# VNT.net
KiCad netlist of a schematic drawn in EAGLE
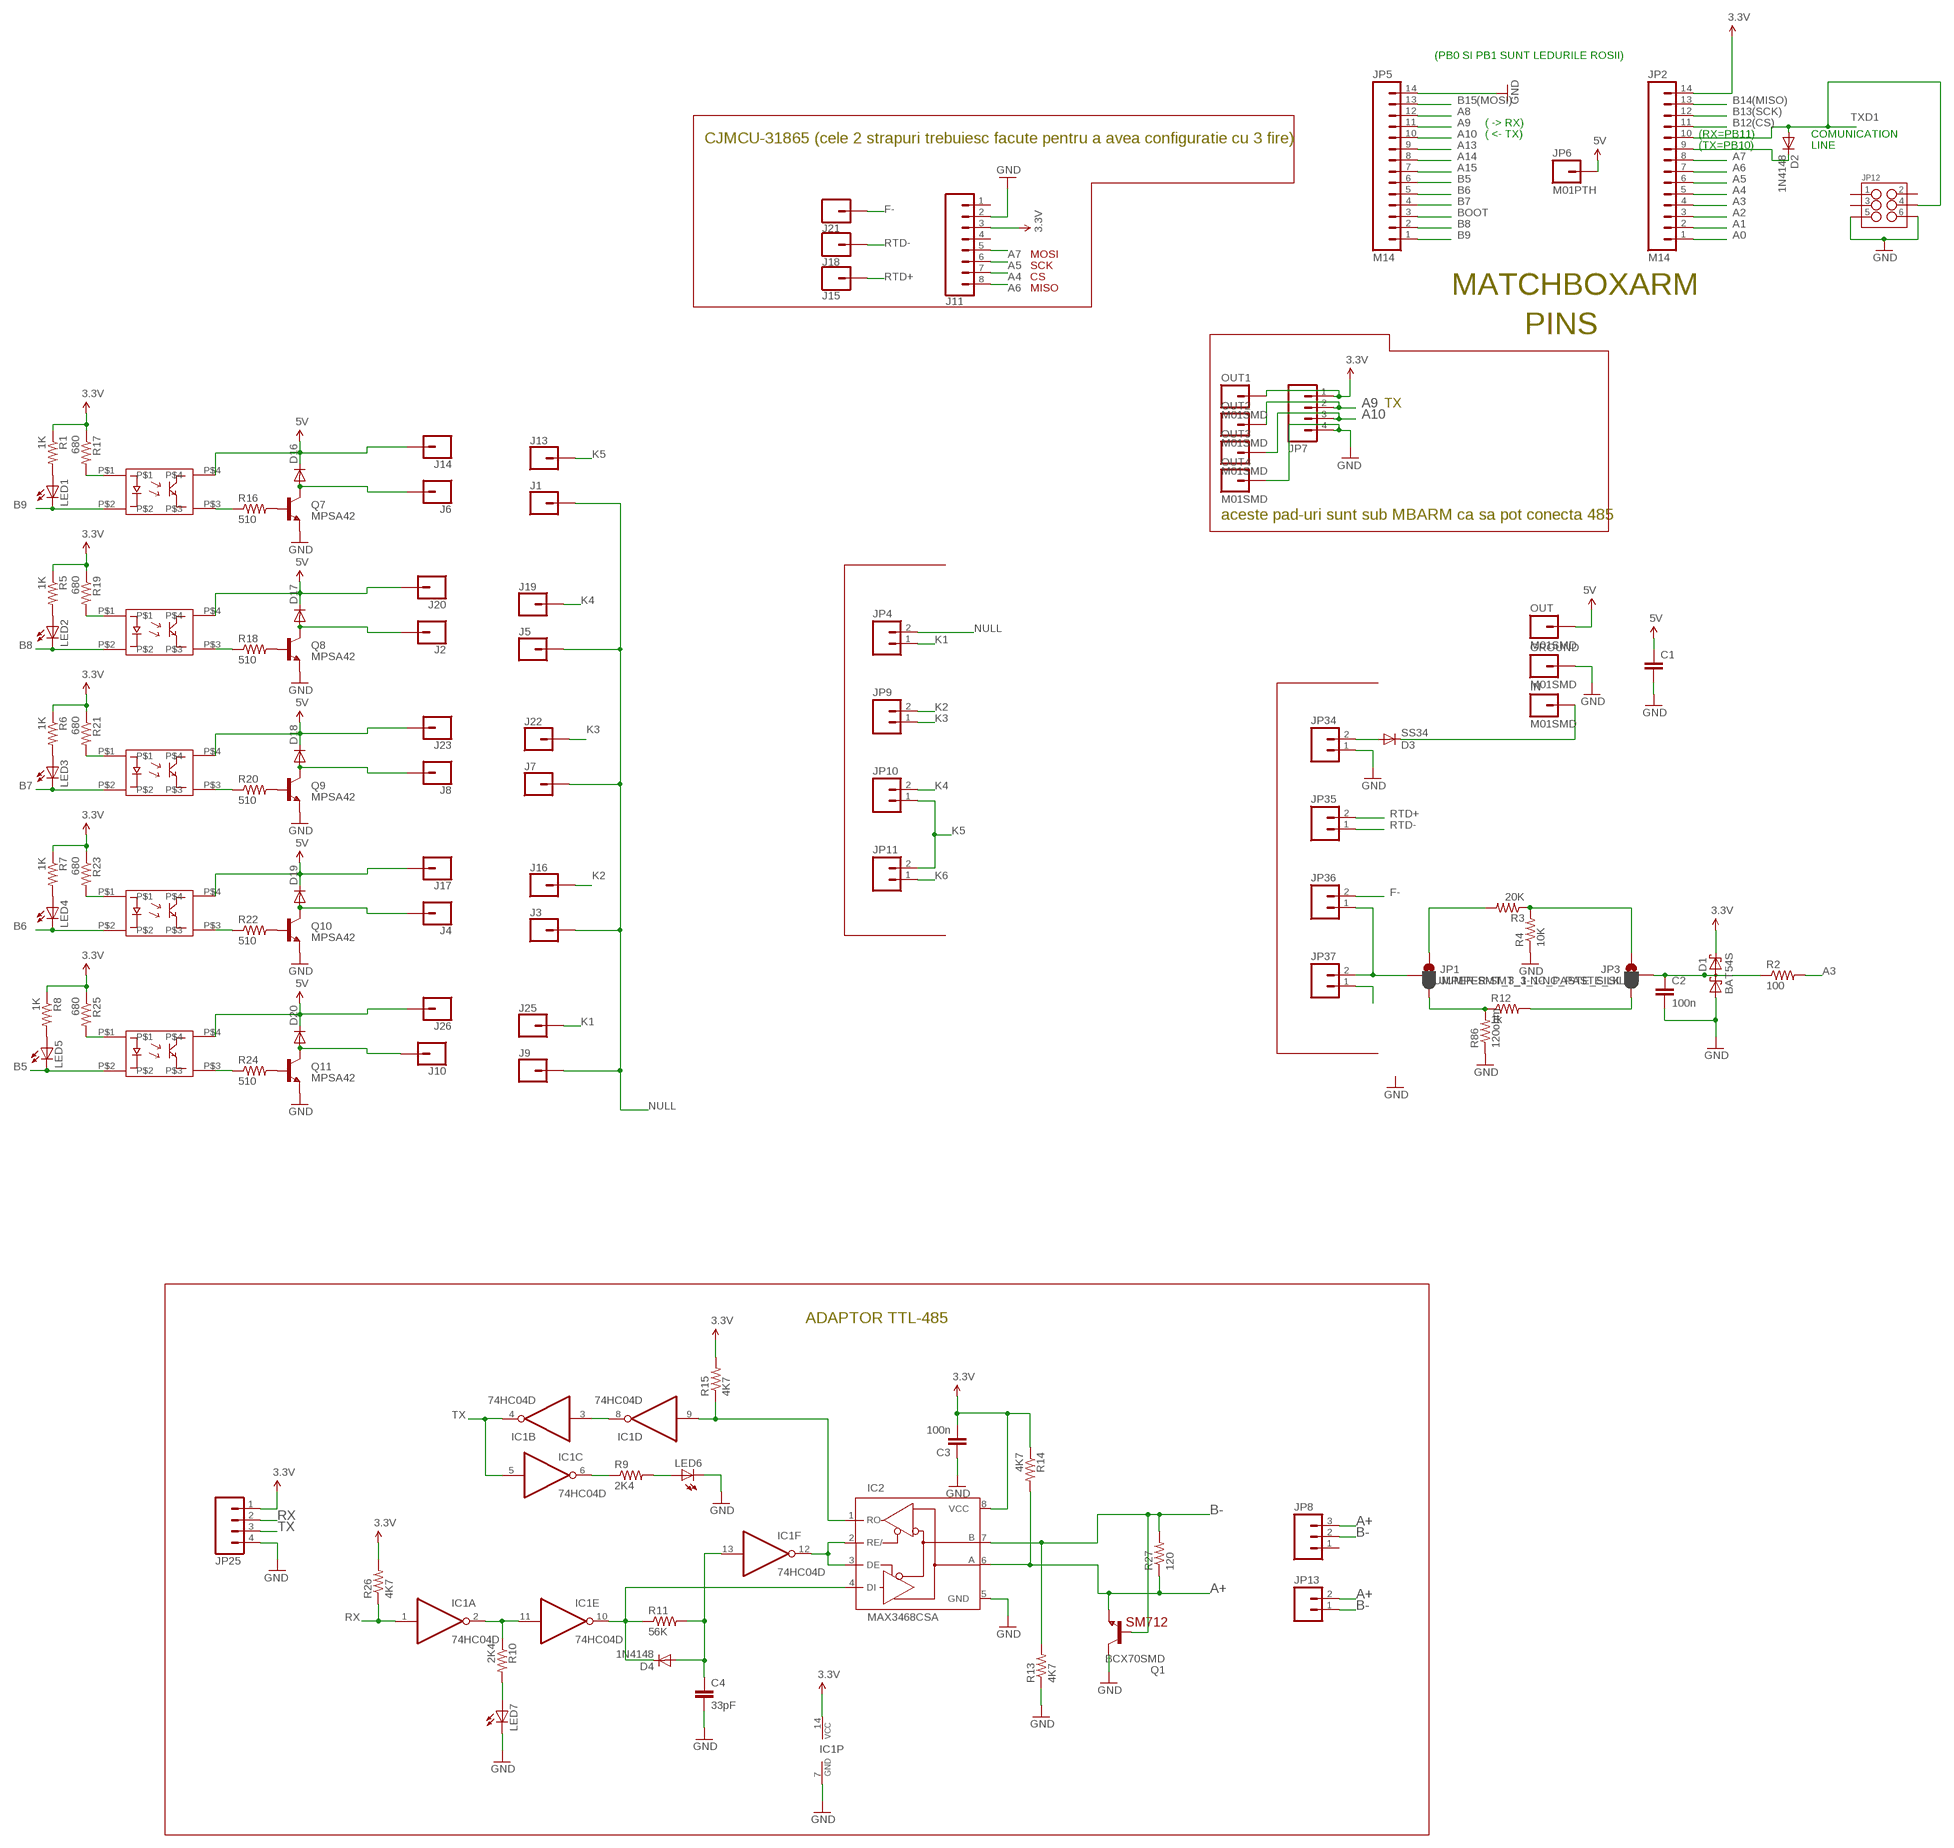
[diagram p0: schematic, sheet 1]

(export (version "E")
  (design (tool "Eeschema 10.0.6"))
  (components
    (comp (ref "C1")
      (value "CAPPTH1")
      (footprint "eagle-import:CAP-PTH-5MM")
      (libsource (lib "eagle-import") (part "CAPPTH1"))
    )
    (comp (ref "C2")
      (value "100n")
      (footprint "eagle-import:0805")
      (libsource (lib "eagle-import") (part "CAP0805"))
    )
    (comp (ref "C3")
      (value "100n")
      (footprint "eagle-import:0805")
      (libsource (lib "eagle-import") (part "CAP0805"))
    )
    (comp (ref "C4")
      (value "33pF")
      (footprint "eagle-import:0805")
      (libsource (lib "eagle-import") (part "CAP0805"))
    )
    (comp (ref "D1")
      (value "BAT54S")
      (footprint "eagle-import:SOT23")
      (libsource (lib "eagle-import") (part "BAT54S"))
    )
    (comp (ref "D2")
      (value "1N4148")
      (footprint "eagle-import:MINIMELF")
      (libsource (lib "eagle-import") (part "DIODE-MINIMELF"))
    )
    (comp (ref "D3")
      (value "SS34")
      (footprint "eagle-import:SMC")
      (libsource (lib "eagle-import") (part "DIODE-SMC"))
    )
    (comp (ref "D4")
      (value "1N4148")
      (footprint "eagle-import:MINIMELF")
      (libsource (lib "eagle-import") (part "DIODE-MINIMELF"))
    )
    (comp (ref "D16")
      (value "DIODE-MINIMELF")
      (footprint "eagle-import:MINIMELF")
      (libsource (lib "eagle-import") (part "diode_NEDELCU_DIODE-MINIMELF"))
    )
    (comp (ref "D17")
      (value "DIODE-MINIMELF")
      (footprint "eagle-import:MINIMELF")
      (libsource (lib "eagle-import") (part "diode_NEDELCU_DIODE-MINIMELF"))
    )
    (comp (ref "D18")
      (value "DIODE-MINIMELF")
      (footprint "eagle-import:MINIMELF")
      (libsource (lib "eagle-import") (part "diode_NEDELCU_DIODE-MINIMELF"))
    )
    (comp (ref "D19")
      (value "DIODE-MINIMELF")
      (footprint "eagle-import:MINIMELF")
      (libsource (lib "eagle-import") (part "diode_NEDELCU_DIODE-MINIMELF"))
    )
    (comp (ref "D20")
      (value "DIODE-MINIMELF")
      (footprint "eagle-import:MINIMELF")
      (libsource (lib "eagle-import") (part "diode_NEDELCU_DIODE-MINIMELF"))
    )
    (comp (ref "GROUND")
      (value "M01SMD")
      (footprint "eagle-import:LUXEON-PAD")
      (libsource (lib "eagle-import") (part "M01SMD"))
    )
    (comp (ref "IC1")
      (value "74HC04D")
      (footprint "eagle-import:SO14")
      (libsource (lib "eagle-import") (part "7404DHC"))
    )
    (comp (ref "IC2")
      (value "MAX3468CSA")
      (footprint "eagle-import:SO08")
      (fields (field (name "MPN") "MAX3468CSA+"))
      (libsource (lib "eagle-import") (part "MAX34SA68C"))
    )
    (comp (ref "IN")
      (value "M01SMD")
      (footprint "eagle-import:LUXEON-PAD")
      (libsource (lib "eagle-import") (part "M01SMD"))
    )
    (comp (ref "J1")
      (value "CONN_01")
      (footprint "eagle-import:1X01@2")
      (libsource (lib "eagle-import") (part "CONN_01"))
    )
    (comp (ref "J2")
      (value "CONN_01")
      (footprint "eagle-import:1X01@2")
      (libsource (lib "eagle-import") (part "CONN_01"))
    )
    (comp (ref "J3")
      (value "CONN_01")
      (footprint "eagle-import:1X01@2")
      (libsource (lib "eagle-import") (part "CONN_01"))
    )
    (comp (ref "J4")
      (value "CONN_01")
      (footprint "eagle-import:1X01@2")
      (libsource (lib "eagle-import") (part "CONN_01"))
    )
    (comp (ref "J5")
      (value "CONN_01")
      (footprint "eagle-import:1X01@2")
      (libsource (lib "eagle-import") (part "CONN_01"))
    )
    (comp (ref "J6")
      (value "CONN_01")
      (footprint "eagle-import:1X01@2")
      (libsource (lib "eagle-import") (part "CONN_01"))
    )
    (comp (ref "J7")
      (value "CONN_01")
      (footprint "eagle-import:1X01@2")
      (libsource (lib "eagle-import") (part "CONN_01"))
    )
    (comp (ref "J8")
      (value "CONN_01")
      (footprint "eagle-import:1X01@2")
      (libsource (lib "eagle-import") (part "CONN_01"))
    )
    (comp (ref "J9")
      (value "CONN_01")
      (footprint "eagle-import:1X01@2")
      (libsource (lib "eagle-import") (part "CONN_01"))
    )
    (comp (ref "J10")
      (value "CONN_01")
      (footprint "eagle-import:1X01@2")
      (libsource (lib "eagle-import") (part "CONN_01"))
    )
    (comp (ref "J11")
      (value "CONN_08LOCK")
      (footprint "eagle-import:1X08_LOCK")
      (libsource (lib "eagle-import") (part "CONN_08LOCK"))
    )
    (comp (ref "J13")
      (value "CONN_01")
      (footprint "eagle-import:1X01@2")
      (libsource (lib "eagle-import") (part "CONN_01"))
    )
    (comp (ref "J14")
      (value "CONN_01")
      (footprint "eagle-import:1X01@2")
      (libsource (lib "eagle-import") (part "CONN_01"))
    )
    (comp (ref "J15")
      (value "CONN_01")
      (footprint "eagle-import:1X01@2")
      (libsource (lib "eagle-import") (part "CONN_01"))
    )
    (comp (ref "J16")
      (value "CONN_01")
      (footprint "eagle-import:1X01@2")
      (libsource (lib "eagle-import") (part "CONN_01"))
    )
    (comp (ref "J17")
      (value "CONN_01")
      (footprint "eagle-import:1X01@2")
      (libsource (lib "eagle-import") (part "CONN_01"))
    )
    (comp (ref "J18")
      (value "CONN_01")
      (footprint "eagle-import:1X01@2")
      (libsource (lib "eagle-import") (part "CONN_01"))
    )
    (comp (ref "J19")
      (value "CONN_01")
      (footprint "eagle-import:1X01@2")
      (libsource (lib "eagle-import") (part "CONN_01"))
    )
    (comp (ref "J20")
      (value "CONN_01")
      (footprint "eagle-import:1X01@2")
      (libsource (lib "eagle-import") (part "CONN_01"))
    )
    (comp (ref "J21")
      (value "CONN_01")
      (footprint "eagle-import:1X01@2")
      (libsource (lib "eagle-import") (part "CONN_01"))
    )
    (comp (ref "J22")
      (value "CONN_01")
      (footprint "eagle-import:1X01@2")
      (libsource (lib "eagle-import") (part "CONN_01"))
    )
    (comp (ref "J23")
      (value "CONN_01")
      (footprint "eagle-import:1X01@2")
      (libsource (lib "eagle-import") (part "CONN_01"))
    )
    (comp (ref "J25")
      (value "CONN_01")
      (footprint "eagle-import:1X01@2")
      (libsource (lib "eagle-import") (part "CONN_01"))
    )
    (comp (ref "J26")
      (value "CONN_01")
      (footprint "eagle-import:1X01@2")
      (libsource (lib "eagle-import") (part "CONN_01"))
    )
    (comp (ref "JP1")
      (value "JUMPER-SMT_3_1-NC_PASTE_SILK")
      (footprint "eagle-import:SMT-JUMPER_3_1-NC_PASTE_SILK")
      (libsource (lib "eagle-import") (part "JUMPER-SMT_3_1-NC_PASTE_SILK"))
    )
    (comp (ref "JP2")
      (value "M14")
      (footprint "eagle-import:1X14")
      (libsource (lib "eagle-import") (part "M14"))
    )
    (comp (ref "JP3")
      (value "JUMPER-SMT_3_1-NC_PASTE_SILK")
      (footprint "eagle-import:SMT-JUMPER_3_1-NC_PASTE_SILK")
      (libsource (lib "eagle-import") (part "JUMPER-SMT_3_1-NC_PASTE_SILK"))
    )
    (comp (ref "JP4")
      (value "M025MM")
      (footprint "eagle-import:SCREWTERMINAL-5MM-2")
      (libsource (lib "eagle-import") (part "M025MM"))
    )
    (comp (ref "JP5")
      (value "M14")
      (footprint "eagle-import:1X14")
      (libsource (lib "eagle-import") (part "M14"))
    )
    (comp (ref "JP6")
      (value "M01PTH")
      (footprint "eagle-import:1X01")
      (libsource (lib "eagle-import") (part "M01PTH"))
    )
    (comp (ref "JP7")
      (value "M04PTH")
      (footprint "eagle-import:1X04")
      (libsource (lib "eagle-import") (part "M04PTH"))
    )
    (comp (ref "JP8")
      (value "M03-SCREW-5MM")
      (footprint "eagle-import:SCREWTERMINAL-5MM-3")
      (libsource (lib "eagle-import") (part "M03-SCREW-5MM"))
    )
    (comp (ref "JP9")
      (value "M025MM")
      (footprint "eagle-import:SCREWTERMINAL-5MM-2")
      (libsource (lib "eagle-import") (part "M025MM"))
    )
    (comp (ref "JP10")
      (value "M025MM")
      (footprint "eagle-import:SCREWTERMINAL-5MM-2")
      (libsource (lib "eagle-import") (part "M025MM"))
    )
    (comp (ref "JP11")
      (value "M025MM")
      (footprint "eagle-import:SCREWTERMINAL-5MM-2")
      (libsource (lib "eagle-import") (part "M025MM"))
    )
    (comp (ref "JP12")
      (value "M03X22X3_SILK_MALE_PTH")
      (footprint "eagle-import:2X3")
      (libsource (lib "eagle-import") (part "M03X22X3_SILK_MALE_PTH"))
    )
    (comp (ref "JP13")
      (value "M025MM")
      (footprint "eagle-import:SCREWTERMINAL-5MM-2")
      (libsource (lib "eagle-import") (part "M025MM"))
    )
    (comp (ref "JP25")
      (value "M04PTH")
      (footprint "eagle-import:1X04")
      (libsource (lib "eagle-import") (part "M04PTH"))
    )
    (comp (ref "JP34")
      (value "M025MM")
      (footprint "eagle-import:SCREWTERMINAL-5MM-2")
      (libsource (lib "eagle-import") (part "M025MM"))
    )
    (comp (ref "JP35")
      (value "M025MM")
      (footprint "eagle-import:SCREWTERMINAL-5MM-2")
      (libsource (lib "eagle-import") (part "M025MM"))
    )
    (comp (ref "JP36")
      (value "M025MM")
      (footprint "eagle-import:SCREWTERMINAL-5MM-2")
      (libsource (lib "eagle-import") (part "M025MM"))
    )
    (comp (ref "JP37")
      (value "M025MM")
      (footprint "eagle-import:SCREWTERMINAL-5MM-2")
      (libsource (lib "eagle-import") (part "M025MM"))
    )
    (comp (ref "LED1")
      (value "LEDCHIP-LED0805")
      (footprint "eagle-import:CHIP-LED0805")
      (libsource (lib "eagle-import") (part "LEDCHIP-LED0805"))
    )
    (comp (ref "LED2")
      (value "LEDCHIP-LED0805")
      (footprint "eagle-import:CHIP-LED0805")
      (libsource (lib "eagle-import") (part "LEDCHIP-LED0805"))
    )
    (comp (ref "LED3")
      (value "LEDCHIP-LED0805")
      (footprint "eagle-import:CHIP-LED0805")
      (libsource (lib "eagle-import") (part "LEDCHIP-LED0805"))
    )
    (comp (ref "LED4")
      (value "LEDCHIP-LED0805")
      (footprint "eagle-import:CHIP-LED0805")
      (libsource (lib "eagle-import") (part "LEDCHIP-LED0805"))
    )
    (comp (ref "LED5")
      (value "LEDCHIP-LED0805")
      (footprint "eagle-import:CHIP-LED0805")
      (libsource (lib "eagle-import") (part "LEDCHIP-LED0805"))
    )
    (comp (ref "LED6")
      (value "LEDCHIP-LED0805")
      (footprint "eagle-import:CHIP-LED0805")
      (libsource (lib "eagle-import") (part "LEDCHIP-LED0805"))
    )
    (comp (ref "LED7")
      (value "LEDCHIP-LED0805")
      (footprint "eagle-import:CHIP-LED0805")
      (libsource (lib "eagle-import") (part "LEDCHIP-LED0805"))
    )
    (comp (ref "OUT")
      (value "M01SMD")
      (footprint "eagle-import:LUXEON-PAD")
      (libsource (lib "eagle-import") (part "M01SMD"))
    )
    (comp (ref "OUT1")
      (value "M01SMD")
      (footprint "eagle-import:LUXEON-PAD")
      (libsource (lib "eagle-import") (part "M01SMD"))
    )
    (comp (ref "OUT2")
      (value "M01SMD")
      (footprint "eagle-import:LUXEON-PAD")
      (libsource (lib "eagle-import") (part "M01SMD"))
    )
    (comp (ref "OUT3")
      (value "M01SMD")
      (footprint "eagle-import:LUXEON-PAD")
      (libsource (lib "eagle-import") (part "M01SMD"))
    )
    (comp (ref "OUT4")
      (value "M01SMD")
      (footprint "eagle-import:LUXEON-PAD")
      (libsource (lib "eagle-import") (part "M01SMD"))
    )
    (comp (ref "Q1")
      (value "BCX70SMD")
      (footprint "eagle-import:SOT23")
      (libsource (lib "eagle-import") (part "BCX70SMD"))
    )
    (comp (ref "Q7")
      (value "MPSA42")
      (footprint "eagle-import:SOT23-3")
      (libsource (lib "eagle-import") (part "TRANSISTOR_NPNMPSA42"))
    )
    (comp (ref "Q8")
      (value "MPSA42")
      (footprint "eagle-import:SOT23-3")
      (libsource (lib "eagle-import") (part "TRANSISTOR_NPNMPSA42"))
    )
    (comp (ref "Q9")
      (value "MPSA42")
      (footprint "eagle-import:SOT23-3")
      (libsource (lib "eagle-import") (part "TRANSISTOR_NPNMPSA42"))
    )
    (comp (ref "Q10")
      (value "MPSA42")
      (footprint "eagle-import:SOT23-3")
      (libsource (lib "eagle-import") (part "TRANSISTOR_NPNMPSA42"))
    )
    (comp (ref "Q11")
      (value "MPSA42")
      (footprint "eagle-import:SOT23-3")
      (libsource (lib "eagle-import") (part "TRANSISTOR_NPNMPSA42"))
    )
    (comp (ref "R1")
      (value "1K")
      (footprint "eagle-import:0805")
      (libsource (lib "eagle-import") (part "RESISTOR0805-RES"))
    )
    (comp (ref "R2")
      (value "100")
      (footprint "eagle-import:0805")
      (libsource (lib "eagle-import") (part "RESISTOR0805-RES"))
    )
    (comp (ref "R3")
      (value "20K")
      (footprint "eagle-import:1206")
      (libsource (lib "eagle-import") (part "RESISTOR1206"))
    )
    (comp (ref "R4")
      (value "10K")
      (footprint "eagle-import:1206")
      (libsource (lib "eagle-import") (part "RESISTOR1206"))
    )
    (comp (ref "R5")
      (value "1K")
      (footprint "eagle-import:0805")
      (libsource (lib "eagle-import") (part "RESISTOR0805-RES"))
    )
    (comp (ref "R6")
      (value "1K")
      (footprint "eagle-import:0805")
      (libsource (lib "eagle-import") (part "RESISTOR0805-RES"))
    )
    (comp (ref "R7")
      (value "1K")
      (footprint "eagle-import:0805")
      (libsource (lib "eagle-import") (part "RESISTOR0805-RES"))
    )
    (comp (ref "R8")
      (value "1K")
      (footprint "eagle-import:0805")
      (libsource (lib "eagle-import") (part "RESISTOR0805-RES"))
    )
    (comp (ref "R9")
      (value "2K4")
      (footprint "eagle-import:0805")
      (libsource (lib "eagle-import") (part "RESISTOR0805-RES"))
    )
    (comp (ref "R10")
      (value "2K4")
      (footprint "eagle-import:0805")
      (libsource (lib "eagle-import") (part "RESISTOR0805-RES"))
    )
    (comp (ref "R11")
      (value "56K")
      (footprint "eagle-import:0805")
      (libsource (lib "eagle-import") (part "RESISTOR0805-RES"))
    )
    (comp (ref "R12")
      (value "1k")
      (footprint "eagle-import:0805")
      (libsource (lib "eagle-import") (part "RESISTOR0805-RES"))
    )
    (comp (ref "R13")
      (value "4K7")
      (footprint "eagle-import:0805")
      (libsource (lib "eagle-import") (part "RESISTOR0805-RES"))
    )
    (comp (ref "R14")
      (value "4K7")
      (footprint "eagle-import:0805")
      (libsource (lib "eagle-import") (part "RESISTOR0805-RES"))
    )
    (comp (ref "R15")
      (value "4K7")
      (footprint "eagle-import:0805")
      (libsource (lib "eagle-import") (part "RESISTOR0805-RES"))
    )
    (comp (ref "R16")
      (value "510")
      (footprint "eagle-import:0805")
      (libsource (lib "eagle-import") (part "RESISTOR0805-RES"))
    )
    (comp (ref "R17")
      (value "680")
      (footprint "eagle-import:0805")
      (libsource (lib "eagle-import") (part "RESISTOR0805-RES"))
    )
    (comp (ref "R18")
      (value "510")
      (footprint "eagle-import:0805")
      (libsource (lib "eagle-import") (part "RESISTOR0805-RES"))
    )
    (comp (ref "R19")
      (value "680")
      (footprint "eagle-import:0805")
      (libsource (lib "eagle-import") (part "RESISTOR0805-RES"))
    )
    (comp (ref "R20")
      (value "510")
      (footprint "eagle-import:0805")
      (libsource (lib "eagle-import") (part "RESISTOR0805-RES"))
    )
    (comp (ref "R21")
      (value "680")
      (footprint "eagle-import:0805")
      (libsource (lib "eagle-import") (part "RESISTOR0805-RES"))
    )
    (comp (ref "R22")
      (value "510")
      (footprint "eagle-import:0805")
      (libsource (lib "eagle-import") (part "RESISTOR0805-RES"))
    )
    (comp (ref "R23")
      (value "680")
      (footprint "eagle-import:0805")
      (libsource (lib "eagle-import") (part "RESISTOR0805-RES"))
    )
    (comp (ref "R24")
      (value "510")
      (footprint "eagle-import:0805")
      (libsource (lib "eagle-import") (part "RESISTOR0805-RES"))
    )
    (comp (ref "R25")
      (value "680")
      (footprint "eagle-import:0805")
      (libsource (lib "eagle-import") (part "RESISTOR0805-RES"))
    )
    (comp (ref "R26")
      (value "4K7")
      (footprint "eagle-import:0805")
      (libsource (lib "eagle-import") (part "RESISTOR0805-RES"))
    )
    (comp (ref "R27")
      (value "120")
      (footprint "eagle-import:0805")
      (libsource (lib "eagle-import") (part "RESISTOR0805-RES"))
    )
    (comp (ref "R86")
      (value "120ohm")
      (footprint "eagle-import:R2010")
      (libsource (lib "eagle-import") (part "RESISTOR2010"))
    )
    (comp (ref "U$13")
      (value "IS181D-I")
      (footprint "eagle-import:TLP181-I")
      (libsource (lib "eagle-import") (part "IS181D-I"))
    )
    (comp (ref "U$14")
      (value "IS181D-I")
      (footprint "eagle-import:TLP181-I")
      (libsource (lib "eagle-import") (part "IS181D-I"))
    )
    (comp (ref "U$15")
      (value "IS181D-I")
      (footprint "eagle-import:TLP181-I")
      (libsource (lib "eagle-import") (part "IS181D-I"))
    )
    (comp (ref "U$16")
      (value "IS181D-I")
      (footprint "eagle-import:TLP181-I")
      (libsource (lib "eagle-import") (part "IS181D-I"))
    )
    (comp (ref "U$17")
      (value "IS181D-I")
      (footprint "eagle-import:TLP181-I")
      (libsource (lib "eagle-import") (part "IS181D-I"))
    )
  )
  (nets
    (net (code "1") (name "/A+") (class "Default")
      (node (ref "IC2") (pin "6") (pinfunction "A_6") (pintype "passive"))
      (node (ref "JP13") (pin "2") (pinfunction "2_2") (pintype "passive"))
      (node (ref "JP8") (pin "3") (pinfunction "3_3") (pintype "passive"))
      (node (ref "Q1") (pin "2") (pinfunction "E_2") (pintype "passive"))
      (node (ref "R14") (pin "2") (pinfunction "2_2") (pintype "passive"))
      (node (ref "R27") (pin "1") (pinfunction "1_1") (pintype "passive"))
    )
    (net (code "2") (name "/A0") (class "Default")
      (node (ref "JP2") (pin "1") (pinfunction "1_1") (pintype "passive"))
    )
    (net (code "3") (name "/A1") (class "Default")
      (node (ref "JP2") (pin "2") (pinfunction "2_2") (pintype "passive"))
    )
    (net (code "4") (name "/A2") (class "Default")
      (node (ref "JP2") (pin "3") (pinfunction "3_3") (pintype "passive"))
    )
    (net (code "5") (name "/A3") (class "Default")
      (node (ref "JP2") (pin "4") (pinfunction "4_4") (pintype "passive"))
      (node (ref "R2") (pin "2") (pinfunction "2_2") (pintype "passive"))
    )
    (net (code "6") (name "/A4") (class "Default")
      (node (ref "J11") (pin "7") (pinfunction "7_7") (pintype "passive"))
      (node (ref "JP2") (pin "5") (pinfunction "5_5") (pintype "passive"))
    )
    (net (code "7") (name "/A5") (class "Default")
      (node (ref "J11") (pin "6") (pinfunction "6_6") (pintype "passive"))
      (node (ref "JP2") (pin "6") (pinfunction "6_6") (pintype "passive"))
    )
    (net (code "8") (name "/A6") (class "Default")
      (node (ref "J11") (pin "8") (pinfunction "8_8") (pintype "passive"))
      (node (ref "JP2") (pin "7") (pinfunction "7_7") (pintype "passive"))
    )
    (net (code "9") (name "/A7") (class "Default")
      (node (ref "J11") (pin "5") (pinfunction "5_5") (pintype "passive"))
      (node (ref "JP2") (pin "8") (pinfunction "8_8") (pintype "passive"))
    )
    (net (code "10") (name "/A8") (class "Default")
      (node (ref "JP5") (pin "12") (pinfunction "12_12") (pintype "passive"))
    )
    (net (code "11") (name "/A9") (class "Default")
      (node (ref "JP5") (pin "11") (pinfunction "11_11") (pintype "passive"))
      (node (ref "JP7") (pin "2") (pinfunction "2_2") (pintype "passive"))
      (node (ref "OUT2") (pin "P$1") (pinfunction "1_P$1") (pintype "passive"))
    )
    (net (code "12") (name "/A10") (class "Default")
      (node (ref "JP5") (pin "10") (pinfunction "10_10") (pintype "passive"))
      (node (ref "JP7") (pin "3") (pinfunction "3_3") (pintype "passive"))
      (node (ref "OUT3") (pin "P$1") (pinfunction "1_P$1") (pintype "passive"))
    )
    (net (code "13") (name "/A13") (class "Default")
      (node (ref "JP5") (pin "9") (pinfunction "9_9") (pintype "passive"))
    )
    (net (code "14") (name "/A14") (class "Default")
      (node (ref "JP5") (pin "8") (pinfunction "8_8") (pintype "passive"))
    )
    (net (code "15") (name "/A15") (class "Default")
      (node (ref "JP5") (pin "7") (pinfunction "7_7") (pintype "passive"))
    )
    (net (code "16") (name "/B-") (class "Default")
      (node (ref "IC2") (pin "7") (pinfunction "B_7") (pintype "passive"))
      (node (ref "JP13") (pin "1") (pinfunction "1_1") (pintype "passive"))
      (node (ref "JP8") (pin "2") (pinfunction "2_2") (pintype "passive"))
      (node (ref "Q1") (pin "1") (pinfunction "B_1") (pintype "passive"))
      (node (ref "R13") (pin "2") (pinfunction "2_2") (pintype "passive"))
      (node (ref "R27") (pin "2") (pinfunction "2_2") (pintype "passive"))
    )
    (net (code "17") (name "/B5") (class "Default")
      (node (ref "JP5") (pin "6") (pinfunction "6_6") (pintype "passive"))
      (node (ref "LED5") (pin "C") (pinfunction "C_C") (pintype "passive"))
      (node (ref "U$17") (pin "P$2") (pinfunction "P$2_P$2") (pintype "bidirectional"))
    )
    (net (code "18") (name "/B6") (class "Default")
      (node (ref "JP5") (pin "5") (pinfunction "5_5") (pintype "passive"))
      (node (ref "LED4") (pin "C") (pinfunction "C_C") (pintype "passive"))
      (node (ref "U$16") (pin "P$2") (pinfunction "P$2_P$2") (pintype "bidirectional"))
    )
    (net (code "19") (name "/B7") (class "Default")
      (node (ref "JP5") (pin "4") (pinfunction "4_4") (pintype "passive"))
      (node (ref "LED3") (pin "C") (pinfunction "C_C") (pintype "passive"))
      (node (ref "U$15") (pin "P$2") (pinfunction "P$2_P$2") (pintype "bidirectional"))
    )
    (net (code "20") (name "/B8") (class "Default")
      (node (ref "JP5") (pin "2") (pinfunction "2_2") (pintype "passive"))
      (node (ref "LED2") (pin "C") (pinfunction "C_C") (pintype "passive"))
      (node (ref "U$13") (pin "P$2") (pinfunction "P$2_P$2") (pintype "bidirectional"))
    )
    (net (code "21") (name "/B9") (class "Default")
      (node (ref "JP5") (pin "1") (pinfunction "1_1") (pintype "passive"))
      (node (ref "LED1") (pin "C") (pinfunction "C_C") (pintype "passive"))
      (node (ref "U$14") (pin "P$2") (pinfunction "P$2_P$2") (pintype "bidirectional"))
    )
    (net (code "22") (name "/B12(CS)") (class "Default")
      (node (ref "JP2") (pin "11") (pinfunction "11_11") (pintype "passive"))
    )
    (net (code "23") (name "/B13(SCK)") (class "Default")
      (node (ref "JP2") (pin "12") (pinfunction "12_12") (pintype "passive"))
    )
    (net (code "24") (name "/B14(MISO)") (class "Default")
      (node (ref "JP2") (pin "13") (pinfunction "13_13") (pintype "passive"))
    )
    (net (code "25") (name "/B15(MOSI)") (class "Default")
      (node (ref "JP5") (pin "13") (pinfunction "13_13") (pintype "passive"))
    )
    (net (code "26") (name "/BOOT") (class "Default")
      (node (ref "JP5") (pin "3") (pinfunction "3_3") (pintype "passive"))
    )
    (net (code "27") (name "/F-") (class "Default")
      (node (ref "J21") (pin "1") (pinfunction "1_1") (pintype "passive"))
      (node (ref "JP36") (pin "2") (pinfunction "2_2") (pintype "passive"))
    )
    (net (code "28") (name "/K1") (class "Default")
      (node (ref "J25") (pin "1") (pinfunction "1_1") (pintype "passive"))
      (node (ref "JP4") (pin "1") (pinfunction "1_1") (pintype "passive"))
    )
    (net (code "29") (name "/K2") (class "Default")
      (node (ref "J16") (pin "1") (pinfunction "1_1") (pintype "passive"))
      (node (ref "JP9") (pin "2") (pinfunction "2_2") (pintype "passive"))
    )
    (net (code "30") (name "/K3") (class "Default")
      (node (ref "J22") (pin "1") (pinfunction "1_1") (pintype "passive"))
      (node (ref "JP9") (pin "1") (pinfunction "1_1") (pintype "passive"))
    )
    (net (code "31") (name "/K4") (class "Default")
      (node (ref "J19") (pin "1") (pinfunction "1_1") (pintype "passive"))
      (node (ref "JP10") (pin "2") (pinfunction "2_2") (pintype "passive"))
    )
    (net (code "32") (name "/K5") (class "Default")
      (node (ref "J13") (pin "1") (pinfunction "1_1") (pintype "passive"))
      (node (ref "JP10") (pin "1") (pinfunction "1_1") (pintype "passive"))
      (node (ref "JP11") (pin "2") (pinfunction "2_2") (pintype "passive"))
    )
    (net (code "33") (name "/K6") (class "Default")
      (node (ref "JP11") (pin "1") (pinfunction "1_1") (pintype "passive"))
    )
    (net (code "34") (name "/NULL") (class "Default")
      (node (ref "J1") (pin "1") (pinfunction "1_1") (pintype "passive"))
      (node (ref "J3") (pin "1") (pinfunction "1_1") (pintype "passive"))
      (node (ref "J5") (pin "1") (pinfunction "1_1") (pintype "passive"))
      (node (ref "J7") (pin "1") (pinfunction "1_1") (pintype "passive"))
      (node (ref "J9") (pin "1") (pinfunction "1_1") (pintype "passive"))
      (node (ref "JP4") (pin "2") (pinfunction "2_2") (pintype "passive"))
    )
    (net (code "35") (name "/RTD+") (class "Default")
      (node (ref "J15") (pin "1") (pinfunction "1_1") (pintype "passive"))
      (node (ref "JP35") (pin "2") (pinfunction "2_2") (pintype "passive"))
    )
    (net (code "36") (name "/RTD-") (class "Default")
      (node (ref "J18") (pin "1") (pinfunction "1_1") (pintype "passive"))
      (node (ref "JP35") (pin "1") (pinfunction "1_1") (pintype "passive"))
    )
    (net (code "37") (name "/RX") (class "Default")
      (node (ref "IC1") (pin "1") (pinfunction "I_1") (pintype "input"))
      (node (ref "JP25") (pin "2") (pinfunction "2_2") (pintype "passive"))
      (node (ref "R26") (pin "1") (pinfunction "1_1") (pintype "passive"))
    )
    (net (code "38") (name "/TX") (class "Default")
      (node (ref "IC1") (pin "4") (pinfunction "O_4") (pintype "output"))
      (node (ref "IC1") (pin "5") (pinfunction "I_5") (pintype "input"))
      (node (ref "JP25") (pin "3") (pinfunction "3_3") (pintype "passive"))
    )
    (net (code "39") (name "/TXD1") (class "Default")
      (node (ref "D2") (pin "A") (pinfunction "A_A") (pintype "passive"))
      (node (ref "JP12") (pin "4") (pinfunction "4_4") (pintype "bidirectional"))
      (node (ref "JP2") (pin "10") (pinfunction "10_10") (pintype "passive"))
    )
    (net (code "40") (name "3.3V") (class "Default")
      (node (ref "C3") (pin "2") (pinfunction "2_2") (pintype "passive"))
      (node (ref "D1") (pin "2") (pinfunction "C2_2") (pintype "passive"))
      (node (ref "IC1") (pin "14") (pinfunction "VCC_14") (pintype "power_in"))
      (node (ref "IC2") (pin "8") (pinfunction "VCC_8") (pintype "power_in"))
      (node (ref "J11") (pin "3") (pinfunction "3_3") (pintype "passive"))
      (node (ref "JP2") (pin "14") (pinfunction "14_14") (pintype "passive"))
      (node (ref "JP25") (pin "1") (pinfunction "1_1") (pintype "passive"))
      (node (ref "JP7") (pin "1") (pinfunction "1_1") (pintype "passive"))
      (node (ref "OUT1") (pin "P$1") (pinfunction "1_P$1") (pintype "passive"))
      (node (ref "R1") (pin "1") (pinfunction "1_1") (pintype "passive"))
      (node (ref "R14") (pin "1") (pinfunction "1_1") (pintype "passive"))
      (node (ref "R15") (pin "2") (pinfunction "2_2") (pintype "passive"))
      (node (ref "R17") (pin "1") (pinfunction "1_1") (pintype "passive"))
      (node (ref "R19") (pin "1") (pinfunction "1_1") (pintype "passive"))
      (node (ref "R21") (pin "1") (pinfunction "1_1") (pintype "passive"))
      (node (ref "R23") (pin "1") (pinfunction "1_1") (pintype "passive"))
      (node (ref "R25") (pin "1") (pinfunction "1_1") (pintype "passive"))
      (node (ref "R26") (pin "2") (pinfunction "2_2") (pintype "passive"))
      (node (ref "R5") (pin "1") (pinfunction "1_1") (pintype "passive"))
      (node (ref "R6") (pin "1") (pinfunction "1_1") (pintype "passive"))
      (node (ref "R7") (pin "1") (pinfunction "1_1") (pintype "passive"))
      (node (ref "R8") (pin "1") (pinfunction "1_1") (pintype "passive"))
    )
    (net (code "41") (name "5V") (class "Default")
      (node (ref "C1") (pin "1") (pinfunction "1_1") (pintype "passive"))
      (node (ref "D16") (pin "C") (pinfunction "C_C") (pintype "passive"))
      (node (ref "D17") (pin "C") (pinfunction "C_C") (pintype "passive"))
      (node (ref "D18") (pin "C") (pinfunction "C_C") (pintype "passive"))
      (node (ref "D19") (pin "C") (pinfunction "C_C") (pintype "passive"))
      (node (ref "D20") (pin "C") (pinfunction "C_C") (pintype "passive"))
      (node (ref "J14") (pin "1") (pinfunction "1_1") (pintype "passive"))
      (node (ref "J17") (pin "1") (pinfunction "1_1") (pintype "passive"))
      (node (ref "J20") (pin "1") (pinfunction "1_1") (pintype "passive"))
      (node (ref "J23") (pin "1") (pinfunction "1_1") (pintype "passive"))
      (node (ref "J26") (pin "1") (pinfunction "1_1") (pintype "passive"))
      (node (ref "JP6") (pin "1") (pinfunction "1_1") (pintype "passive"))
      (node (ref "OUT") (pin "P$1") (pinfunction "1_P$1") (pintype "passive"))
      (node (ref "U$13") (pin "P$4") (pinfunction "P$4_P$4") (pintype "bidirectional"))
      (node (ref "U$14") (pin "P$4") (pinfunction "P$4_P$4") (pintype "bidirectional"))
      (node (ref "U$15") (pin "P$4") (pinfunction "P$4_P$4") (pintype "bidirectional"))
      (node (ref "U$16") (pin "P$4") (pinfunction "P$4_P$4") (pintype "bidirectional"))
      (node (ref "U$17") (pin "P$4") (pinfunction "P$4_P$4") (pintype "bidirectional"))
    )
    (net (code "42") (name "GND") (class "Default")
      (node (ref "C1") (pin "2") (pinfunction "2_2") (pintype "passive"))
      (node (ref "C2") (pin "2") (pinfunction "2_2") (pintype "passive"))
      (node (ref "C3") (pin "1") (pinfunction "1_1") (pintype "passive"))
      (node (ref "C4") (pin "2") (pinfunction "2_2") (pintype "passive"))
      (node (ref "D1") (pin "1") (pinfunction "A1_1") (pintype "passive"))
      (node (ref "GROUND") (pin "P$1") (pinfunction "1_P$1") (pintype "passive"))
      (node (ref "IC1") (pin "7") (pinfunction "GND_7") (pintype "power_in"))
      (node (ref "IC2") (pin "5") (pinfunction "GND_5") (pintype "power_in"))
      (node (ref "J11") (pin "2") (pinfunction "2_2") (pintype "passive"))
      (node (ref "JP12") (pin "5") (pinfunction "5_5") (pintype "bidirectional"))
      (node (ref "JP12") (pin "6") (pinfunction "6_6") (pintype "bidirectional"))
      (node (ref "JP25") (pin "4") (pinfunction "4_4") (pintype "passive"))
      (node (ref "JP34") (pin "1") (pinfunction "1_1") (pintype "passive"))
      (node (ref "JP5") (pin "14") (pinfunction "14_14") (pintype "passive"))
      (node (ref "JP7") (pin "4") (pinfunction "4_4") (pintype "passive"))
      (node (ref "LED6") (pin "C") (pinfunction "C_C") (pintype "passive"))
      (node (ref "LED7") (pin "C") (pinfunction "C_C") (pintype "passive"))
      (node (ref "OUT4") (pin "P$1") (pinfunction "1_P$1") (pintype "passive"))
      (node (ref "Q1") (pin "3") (pinfunction "C_3") (pintype "passive"))
      (node (ref "Q10") (pin "2") (pinfunction "E_2") (pintype "passive"))
      (node (ref "Q11") (pin "2") (pinfunction "E_2") (pintype "passive"))
      (node (ref "Q7") (pin "2") (pinfunction "E_2") (pintype "passive"))
      (node (ref "Q8") (pin "2") (pinfunction "E_2") (pintype "passive"))
      (node (ref "Q9") (pin "2") (pinfunction "E_2") (pintype "passive"))
      (node (ref "R13") (pin "1") (pinfunction "1_1") (pintype "passive"))
      (node (ref "R4") (pin "1") (pinfunction "1_1") (pintype "passive"))
      (node (ref "R86") (pin "1") (pinfunction "1_1") (pintype "passive"))
    )
    (net (code "43") (name "Net-(D1-C1A2)") (class "Default")
      (node (ref "C2") (pin "1") (pinfunction "1_1") (pintype "passive"))
      (node (ref "D1") (pin "3") (pinfunction "C1A2_3") (pintype "passive"))
      (node (ref "JP3") (pin "2") (pinfunction "2_2") (pintype "passive"))
      (node (ref "R2") (pin "1") (pinfunction "1_1") (pintype "passive"))
    )
    (net (code "44") (name "Net-(D2-PadC)") (class "Default")
      (node (ref "D2") (pin "C") (pinfunction "C_C") (pintype "passive"))
      (node (ref "JP2") (pin "9") (pinfunction "9_9") (pintype "passive"))
    )
    (net (code "45") (name "Net-(D3-PadA)") (class "Default")
      (node (ref "D3") (pin "A") (pinfunction "A_A") (pintype "passive"))
      (node (ref "JP34") (pin "2") (pinfunction "2_2") (pintype "passive"))
    )
    (net (code "46") (name "Net-(IC1A-O)") (class "Default")
      (node (ref "IC1") (pin "11") (pinfunction "I_11") (pintype "input"))
      (node (ref "IC1") (pin "2") (pinfunction "O_2") (pintype "output"))
      (node (ref "R10") (pin "1") (pinfunction "1_1") (pintype "passive"))
    )
    (net (code "47") (name "Net-(IC1B-I)") (class "Default")
      (node (ref "IC1") (pin "3") (pinfunction "I_3") (pintype "input"))
      (node (ref "IC1") (pin "8") (pinfunction "O_8") (pintype "output"))
    )
    (net (code "48") (name "Net-(IC1C-O)") (class "Default")
      (node (ref "IC1") (pin "6") (pinfunction "O_6") (pintype "output"))
      (node (ref "R9") (pin "1") (pinfunction "1_1") (pintype "passive"))
    )
    (net (code "49") (name "Net-(IC1D-I)") (class "Default")
      (node (ref "IC1") (pin "9") (pinfunction "I_9") (pintype "input"))
      (node (ref "IC2") (pin "1") (pinfunction "RO_1") (pintype "output"))
      (node (ref "R15") (pin "1") (pinfunction "1_1") (pintype "passive"))
    )
    (net (code "50") (name "Net-(IC1E-O)") (class "Default")
      (node (ref "D4") (pin "C") (pinfunction "C_C") (pintype "passive"))
      (node (ref "IC1") (pin "10") (pinfunction "O_10") (pintype "output"))
      (node (ref "IC2") (pin "4") (pinfunction "DI_4") (pintype "input"))
      (node (ref "R11") (pin "1") (pinfunction "1_1") (pintype "passive"))
    )
    (net (code "51") (name "Net-(IC1F-I)") (class "Default")
      (node (ref "C4") (pin "1") (pinfunction "1_1") (pintype "passive"))
      (node (ref "D4") (pin "A") (pinfunction "A_A") (pintype "passive"))
      (node (ref "IC1") (pin "13") (pinfunction "I_13") (pintype "input"))
      (node (ref "R11") (pin "2") (pinfunction "2_2") (pintype "passive"))
    )
    (net (code "52") (name "Net-(IC1F-O)") (class "Default")
      (node (ref "IC1") (pin "12") (pinfunction "O_12") (pintype "output"))
      (node (ref "IC2") (pin "2") (pinfunction "RE/_2") (pintype "input"))
      (node (ref "IC2") (pin "3") (pinfunction "DE_3") (pintype "input"))
    )
    (net (code "53") (name "Net-(IN-1)") (class "Default")
      (node (ref "D3") (pin "C") (pinfunction "C_C") (pintype "passive"))
      (node (ref "IN") (pin "P$1") (pinfunction "1_P$1") (pintype "passive"))
    )
    (net (code "54") (name "Net-(JP1-Pad1)") (class "Default")
      (node (ref "JP1") (pin "1") (pinfunction "1_1") (pintype "passive"))
      (node (ref "R3") (pin "2") (pinfunction "2_2") (pintype "passive"))
    )
    (net (code "55") (name "Net-(JP1-Pad2)") (class "Default")
      (node (ref "JP1") (pin "2") (pinfunction "2_2") (pintype "passive"))
      (node (ref "JP36") (pin "1") (pinfunction "1_1") (pintype "passive"))
      (node (ref "JP37") (pin "2") (pinfunction "2_2") (pintype "passive"))
    )
    (net (code "56") (name "Net-(JP1-Pad3)") (class "Default")
      (node (ref "JP1") (pin "3") (pinfunction "3_3") (pintype "passive"))
      (node (ref "R12") (pin "1") (pinfunction "1_1") (pintype "passive"))
      (node (ref "R86") (pin "2") (pinfunction "2_2") (pintype "passive"))
    )
    (net (code "57") (name "Net-(JP3-Pad1)") (class "Default")
      (node (ref "JP3") (pin "1") (pinfunction "1_1") (pintype "passive"))
      (node (ref "R3") (pin "1") (pinfunction "1_1") (pintype "passive"))
      (node (ref "R4") (pin "2") (pinfunction "2_2") (pintype "passive"))
    )
    (net (code "58") (name "Net-(JP3-Pad3)") (class "Default")
      (node (ref "JP3") (pin "3") (pinfunction "3_3") (pintype "passive"))
      (node (ref "R12") (pin "2") (pinfunction "2_2") (pintype "passive"))
    )
    (net (code "59") (name "Net-(LED1-PadA)") (class "Default")
      (node (ref "LED1") (pin "A") (pinfunction "A_A") (pintype "passive"))
      (node (ref "R1") (pin "2") (pinfunction "2_2") (pintype "passive"))
    )
    (net (code "60") (name "Net-(LED2-PadA)") (class "Default")
      (node (ref "LED2") (pin "A") (pinfunction "A_A") (pintype "passive"))
      (node (ref "R5") (pin "2") (pinfunction "2_2") (pintype "passive"))
    )
    (net (code "61") (name "Net-(LED3-PadA)") (class "Default")
      (node (ref "LED3") (pin "A") (pinfunction "A_A") (pintype "passive"))
      (node (ref "R6") (pin "2") (pinfunction "2_2") (pintype "passive"))
    )
    (net (code "62") (name "Net-(LED4-PadA)") (class "Default")
      (node (ref "LED4") (pin "A") (pinfunction "A_A") (pintype "passive"))
      (node (ref "R7") (pin "2") (pinfunction "2_2") (pintype "passive"))
    )
    (net (code "63") (name "Net-(LED5-PadA)") (class "Default")
      (node (ref "LED5") (pin "A") (pinfunction "A_A") (pintype "passive"))
      (node (ref "R8") (pin "2") (pinfunction "2_2") (pintype "passive"))
    )
    (net (code "64") (name "Net-(LED6-PadA)") (class "Default")
      (node (ref "LED6") (pin "A") (pinfunction "A_A") (pintype "passive"))
      (node (ref "R9") (pin "2") (pinfunction "2_2") (pintype "passive"))
    )
    (net (code "65") (name "Net-(LED7-PadA)") (class "Default")
      (node (ref "LED7") (pin "A") (pinfunction "A_A") (pintype "passive"))
      (node (ref "R10") (pin "2") (pinfunction "2_2") (pintype "passive"))
    )
    (net (code "66") (name "Net-(Q7-B)") (class "Default")
      (node (ref "Q7") (pin "1") (pinfunction "B_1") (pintype "passive"))
      (node (ref "R16") (pin "2") (pinfunction "2_2") (pintype "passive"))
    )
    (net (code "67") (name "Net-(Q7-C)") (class "Default")
      (node (ref "D16") (pin "A") (pinfunction "A_A") (pintype "passive"))
      (node (ref "J6") (pin "1") (pinfunction "1_1") (pintype "passive"))
      (node (ref "Q7") (pin "3") (pinfunction "C_3") (pintype "passive"))
    )
    (net (code "68") (name "Net-(Q8-B)") (class "Default")
      (node (ref "Q8") (pin "1") (pinfunction "B_1") (pintype "passive"))
      (node (ref "R18") (pin "2") (pinfunction "2_2") (pintype "passive"))
    )
    (net (code "69") (name "Net-(Q8-C)") (class "Default")
      (node (ref "D17") (pin "A") (pinfunction "A_A") (pintype "passive"))
      (node (ref "J2") (pin "1") (pinfunction "1_1") (pintype "passive"))
      (node (ref "Q8") (pin "3") (pinfunction "C_3") (pintype "passive"))
    )
    (net (code "70") (name "Net-(Q9-B)") (class "Default")
      (node (ref "Q9") (pin "1") (pinfunction "B_1") (pintype "passive"))
      (node (ref "R20") (pin "2") (pinfunction "2_2") (pintype "passive"))
    )
    (net (code "71") (name "Net-(Q9-C)") (class "Default")
      (node (ref "D18") (pin "A") (pinfunction "A_A") (pintype "passive"))
      (node (ref "J8") (pin "1") (pinfunction "1_1") (pintype "passive"))
      (node (ref "Q9") (pin "3") (pinfunction "C_3") (pintype "passive"))
    )
    (net (code "72") (name "Net-(Q10-B)") (class "Default")
      (node (ref "Q10") (pin "1") (pinfunction "B_1") (pintype "passive"))
      (node (ref "R22") (pin "2") (pinfunction "2_2") (pintype "passive"))
    )
    (net (code "73") (name "Net-(Q10-C)") (class "Default")
      (node (ref "D19") (pin "A") (pinfunction "A_A") (pintype "passive"))
      (node (ref "J4") (pin "1") (pinfunction "1_1") (pintype "passive"))
      (node (ref "Q10") (pin "3") (pinfunction "C_3") (pintype "passive"))
    )
    (net (code "74") (name "Net-(Q11-B)") (class "Default")
      (node (ref "Q11") (pin "1") (pinfunction "B_1") (pintype "passive"))
      (node (ref "R24") (pin "2") (pinfunction "2_2") (pintype "passive"))
    )
    (net (code "75") (name "Net-(Q11-C)") (class "Default")
      (node (ref "D20") (pin "A") (pinfunction "A_A") (pintype "passive"))
      (node (ref "J10") (pin "1") (pinfunction "1_1") (pintype "passive"))
      (node (ref "Q11") (pin "3") (pinfunction "C_3") (pintype "passive"))
    )
    (net (code "76") (name "Net-(R16-Pad1)") (class "Default")
      (node (ref "R16") (pin "1") (pinfunction "1_1") (pintype "passive"))
      (node (ref "U$14") (pin "P$3") (pinfunction "P$3_P$3") (pintype "bidirectional"))
    )
    (net (code "77") (name "Net-(R17-Pad2)") (class "Default")
      (node (ref "R17") (pin "2") (pinfunction "2_2") (pintype "passive"))
      (node (ref "U$14") (pin "P$1") (pinfunction "P$1_P$1") (pintype "bidirectional"))
    )
    (net (code "78") (name "Net-(R18-Pad1)") (class "Default")
      (node (ref "R18") (pin "1") (pinfunction "1_1") (pintype "passive"))
      (node (ref "U$13") (pin "P$3") (pinfunction "P$3_P$3") (pintype "bidirectional"))
    )
    (net (code "79") (name "Net-(R19-Pad2)") (class "Default")
      (node (ref "R19") (pin "2") (pinfunction "2_2") (pintype "passive"))
      (node (ref "U$13") (pin "P$1") (pinfunction "P$1_P$1") (pintype "bidirectional"))
    )
    (net (code "80") (name "Net-(R20-Pad1)") (class "Default")
      (node (ref "R20") (pin "1") (pinfunction "1_1") (pintype "passive"))
      (node (ref "U$15") (pin "P$3") (pinfunction "P$3_P$3") (pintype "bidirectional"))
    )
    (net (code "81") (name "Net-(R21-Pad2)") (class "Default")
      (node (ref "R21") (pin "2") (pinfunction "2_2") (pintype "passive"))
      (node (ref "U$15") (pin "P$1") (pinfunction "P$1_P$1") (pintype "bidirectional"))
    )
    (net (code "82") (name "Net-(R22-Pad1)") (class "Default")
      (node (ref "R22") (pin "1") (pinfunction "1_1") (pintype "passive"))
      (node (ref "U$16") (pin "P$3") (pinfunction "P$3_P$3") (pintype "bidirectional"))
    )
    (net (code "83") (name "Net-(R23-Pad2)") (class "Default")
      (node (ref "R23") (pin "2") (pinfunction "2_2") (pintype "passive"))
      (node (ref "U$16") (pin "P$1") (pinfunction "P$1_P$1") (pintype "bidirectional"))
    )
    (net (code "84") (name "Net-(R24-Pad1)") (class "Default")
      (node (ref "R24") (pin "1") (pinfunction "1_1") (pintype "passive"))
      (node (ref "U$17") (pin "P$3") (pinfunction "P$3_P$3") (pintype "bidirectional"))
    )
    (net (code "85") (name "Net-(R25-Pad2)") (class "Default")
      (node (ref "R25") (pin "2") (pinfunction "2_2") (pintype "passive"))
      (node (ref "U$17") (pin "P$1") (pinfunction "P$1_P$1") (pintype "bidirectional"))
    )
    (net (code "86") (name "unconnected-(J11-Pad1)") (class "Default")
      (node (ref "J11") (pin "1") (pinfunction "1_1") (pintype "passive"))
    )
    (net (code "87") (name "unconnected-(J11-Pad4)") (class "Default")
      (node (ref "J11") (pin "4") (pinfunction "4_4") (pintype "passive"))
    )
    (net (code "88") (name "unconnected-(JP8-Pad1)") (class "Default")
      (node (ref "JP8") (pin "1") (pinfunction "1_1") (pintype "passive"))
    )
    (net (code "89") (name "unconnected-(JP12-Pad1)") (class "Default")
      (node (ref "JP12") (pin "1") (pinfunction "1_1") (pintype "bidirectional"))
    )
    (net (code "90") (name "unconnected-(JP12-Pad2)") (class "Default")
      (node (ref "JP12") (pin "2") (pinfunction "2_2") (pintype "bidirectional"))
    )
    (net (code "91") (name "unconnected-(JP12-Pad3)") (class "Default")
      (node (ref "JP12") (pin "3") (pinfunction "3_3") (pintype "bidirectional"))
    )
    (net (code "92") (name "unconnected-(JP37-Pad1)") (class "Default")
      (node (ref "JP37") (pin "1") (pinfunction "1_1") (pintype "passive"))
    )
  )
)
